# Controller.net
KiCad netlist of a schematic drawn in Altium Designer
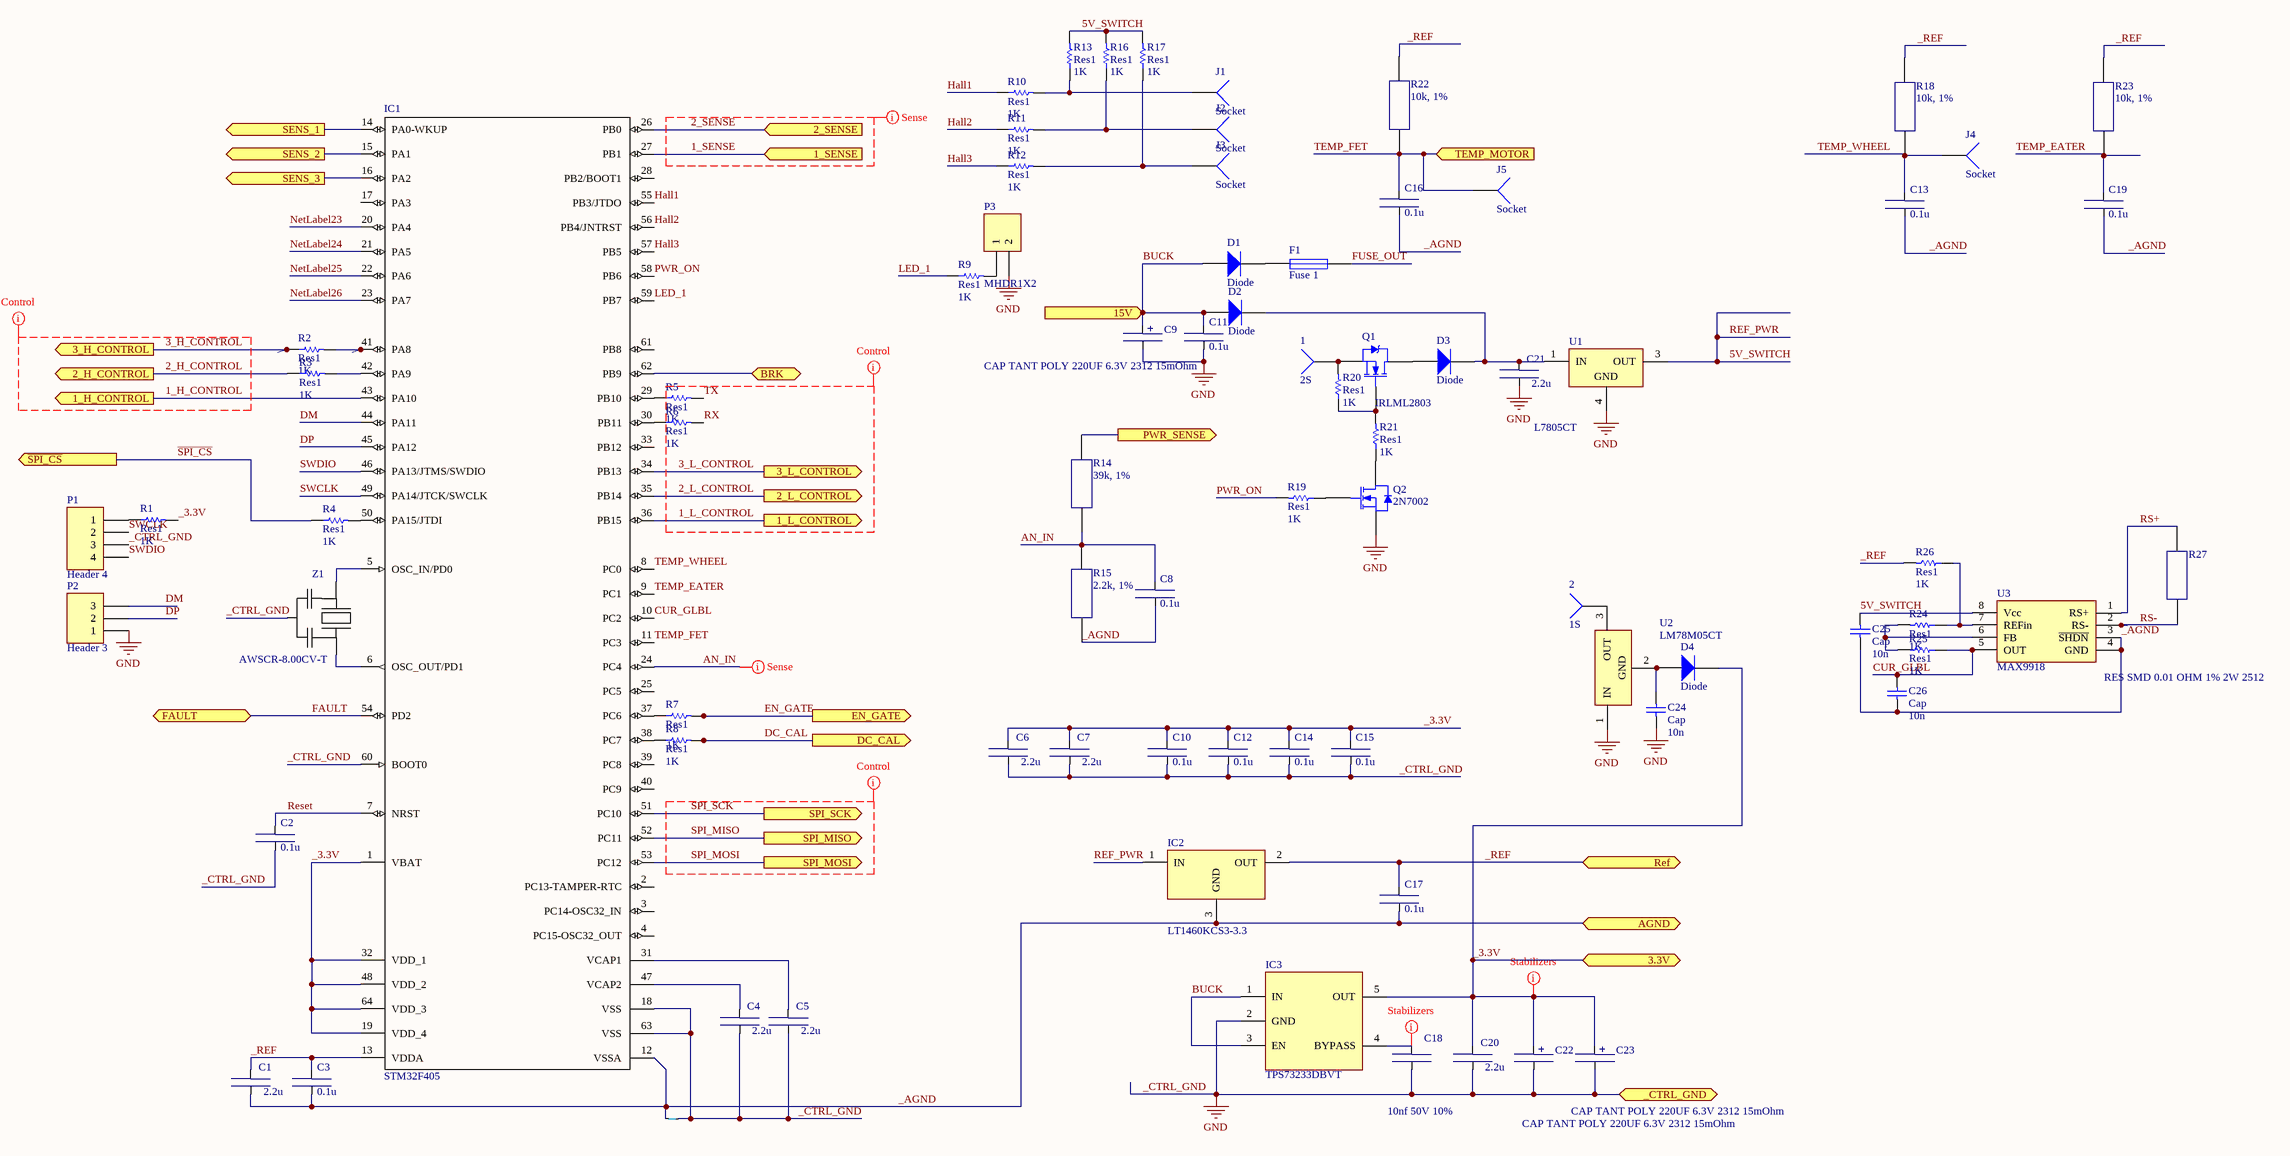
[diagram p0: Controller.SchDoc]

(export (version "E")
  (design (tool "Eeschema 10.0.6"))
  (components
    (comp (ref "1")
      (value "2S")
      (footprint "PIN1")
      (description "Socket")
      (fields (field (name "PUBLISHER") "Altium Limited"))
      (libsource (lib "Miscellaneous Connectors") (part "Socket"))
    )
    (comp (ref "2")
      (value "1S")
      (footprint "PIN1")
      (description "Socket")
      (fields (field (name "PUBLISHER") "Altium Limited"))
      (libsource (lib "Miscellaneous Connectors") (part "Socket"))
    )
    (comp (ref "C1")
      (value "2.2u")
      (footprint "ERA-0603")
      (libsource (lib "Condensator") (part "Ceramic Chip Capacitor"))
    )
    (comp (ref "C2")
      (value "0.1u")
      (footprint "Condensator:CAPC1608X08N(0603)")
      (libsource (lib "Condensator") (part "Ceramic Chip Capacitor"))
    )
    (comp (ref "C3")
      (value "0.1u")
      (footprint "ERA-0603")
      (libsource (lib "Condensator") (part "Ceramic Chip Capacitor"))
    )
    (comp (ref "C4")
      (value "2.2u")
      (footprint "Condensator:CAPC1608X08N(0603)")
      (libsource (lib "Condensator") (part "Ceramic Chip Capacitor"))
    )
    (comp (ref "C5")
      (value "2.2u")
      (footprint "Condensator:CAPC1608X08N(0603)")
      (libsource (lib "Condensator") (part "Ceramic Chip Capacitor"))
    )
    (comp (ref "C6")
      (value "2.2u")
      (footprint "Condensator:CAPC1608X08N(0603)")
      (libsource (lib "Condensator") (part "Ceramic Chip Capacitor"))
    )
    (comp (ref "C7")
      (value "2.2u")
      (footprint "Condensator:CAPC1608X08N(0603)")
      (libsource (lib "Condensator") (part "Ceramic Chip Capacitor"))
    )
    (comp (ref "C8")
      (value "0.1u")
      (footprint "0603x")
      (libsource (lib "Condensator") (part "Ceramic Chip Capacitor"))
    )
    (comp (ref "C9")
      (value "CAP TANT POLY 220UF 6.3V 2312 15mOhm")
      (footprint "CAP_POLY_330")
      (libsource (lib "Condensator") (part "Tantalum Chip Capacitor"))
    )
    (comp (ref "C10")
      (value "0.1u")
      (footprint "Condensator:CAPC1608X08N(0603)")
      (libsource (lib "Condensator") (part "Ceramic Chip Capacitor"))
    )
    (comp (ref "C11")
      (value "0.1u")
      (footprint "ERA-0603")
      (libsource (lib "Condensator") (part "Ceramic Chip Capacitor"))
    )
    (comp (ref "C12")
      (value "0.1u")
      (footprint "Condensator:CAPC1608X08N(0603)")
      (libsource (lib "Condensator") (part "Ceramic Chip Capacitor"))
    )
    (comp (ref "C13")
      (value "0.1u")
      (footprint "0603x")
      (libsource (lib "Condensator") (part "Ceramic Chip Capacitor"))
    )
    (comp (ref "C14")
      (value "0.1u")
      (footprint "Condensator:CAPC1608X08N(0603)")
      (libsource (lib "Condensator") (part "Ceramic Chip Capacitor"))
    )
    (comp (ref "C15")
      (value "0.1u")
      (footprint "Condensator:CAPC1608X08N(0603)")
      (libsource (lib "Condensator") (part "Ceramic Chip Capacitor"))
    )
    (comp (ref "C16")
      (value "0.1u")
      (footprint "Condensator:CAPC1608X08N(0603)")
      (libsource (lib "Condensator") (part "Ceramic Chip Capacitor"))
    )
    (comp (ref "C17")
      (value "0.1u")
      (footprint "0603x")
      (libsource (lib "Condensator") (part "Ceramic Chip Capacitor"))
    )
    (comp (ref "C18")
      (value "10nf 50V 10%")
      (footprint "0603x")
      (libsource (lib "Condensator") (part "Ceramic Chip Capacitor"))
    )
    (comp (ref "C19")
      (value "0.1u")
      (footprint "0603x")
      (libsource (lib "Condensator") (part "Ceramic Chip Capacitor"))
    )
    (comp (ref "C20")
      (value "2.2u")
      (footprint "Condensator:CAPC1608X08N(0603)")
      (libsource (lib "Condensator") (part "Ceramic Chip Capacitor"))
    )
    (comp (ref "C21")
      (value "2.2u")
      (footprint "0603x")
      (libsource (lib "Condensator") (part "Ceramic Chip Capacitor"))
    )
    (comp (ref "C22")
      (value "CAP TANT POLY 220UF 6.3V 2312 15mOhm")
      (footprint "C")
      (libsource (lib "Condensator") (part "Tantalum Chip Capacitor"))
    )
    (comp (ref "C23")
      (value "CAP TANT POLY 220UF 6.3V 2312 15mOhm")
      (footprint "CAP_POLY_330")
      (libsource (lib "Condensator") (part "Tantalum Chip Capacitor"))
    )
    (comp (ref "C24")
      (value "Cap")
      (footprint "ERA-0603")
      (description "Capacitor")
      (fields (field (name "ALTIUM_VALUE") "10n") (field (name "PUBLISHER") "Altium Limited"))
      (libsource (lib "Miscellaneous Devices") (part "Cap"))
    )
    (comp (ref "C25")
      (value "Cap")
      (footprint "ERA-0603")
      (description "Capacitor")
      (fields (field (name "ALTIUM_VALUE") "10n") (field (name "PUBLISHER") "Altium Limited"))
      (libsource (lib "Miscellaneous Devices") (part "Cap"))
    )
    (comp (ref "C26")
      (value "Cap")
      (footprint "ERA-0603")
      (description "Capacitor")
      (fields (field (name "ALTIUM_VALUE") "10n") (field (name "PUBLISHER") "Altium Limited"))
      (libsource (lib "Miscellaneous Devices") (part "Cap"))
    )
    (comp (ref "D1")
      (value "Diode")
      (footprint "SMB_real")
      (description "Default Diode")
      (fields (field (name "PUBLISHER") "Altium Limited"))
      (libsource (lib "Miscellaneous Devices") (part "Diode"))
    )
    (comp (ref "D2")
      (value "Diode")
      (footprint "SMA")
      (description "Default Diode")
      (fields (field (name "PUBLISHER") "Altium Limited"))
      (libsource (lib "Miscellaneous Devices") (part "Diode"))
    )
    (comp (ref "D3")
      (value "Diode")
      (footprint "SMA")
      (description "Default Diode")
      (fields (field (name "PUBLISHER") "Altium Limited"))
      (libsource (lib "Miscellaneous Devices") (part "Diode"))
    )
    (comp (ref "D4")
      (value "Diode")
      (footprint "SMA")
      (description "Default Diode")
      (fields (field (name "PUBLISHER") "Altium Limited"))
      (libsource (lib "Miscellaneous Devices") (part "Diode"))
    )
    (comp (ref "F1")
      (value "Fuse 1")
      (footprint "1812")
      (description "Fuse")
      (fields (field (name "PUBLISHER") "Altium Limited"))
      (libsource (lib "Miscellaneous Devices") (part "Fuse 1"))
    )
    (comp (ref "IC1")
      (value "STM32F405")
      (footprint "LQFP64_L")
      (description "STM32 ARM-based 32-bit MCU")
      (libsource (lib "Mikrosxema") (part "STM32F405"))
    )
    (comp (ref "IC2")
      (value "LT1460KCS3-3.3")
      (footprint "SOT23-3_L")
      (libsource (lib "CustomLib") (part "PreciseRef"))
    )
    (comp (ref "IC3")
      (value "TPS73233DBVT")
      (footprint "SOT23-5_L")
      (libsource (lib "CustomLib") (part "TPS7xx33"))
    )
    (comp (ref "J1")
      (value "Socket")
      (footprint "PIN1")
      (fields (field (name "PUBLISHER") "Altium Limited"))
      (libsource (lib "Miscellaneous Connectors") (part "Socket"))
    )
    (comp (ref "J2")
      (value "Socket")
      (footprint "PIN1")
      (fields (field (name "PUBLISHER") "Altium Limited"))
      (libsource (lib "Miscellaneous Connectors") (part "Socket"))
    )
    (comp (ref "J3")
      (value "Socket")
      (footprint "PIN1")
      (fields (field (name "PUBLISHER") "Altium Limited"))
      (libsource (lib "Miscellaneous Connectors") (part "Socket"))
    )
    (comp (ref "J4")
      (value "Socket")
      (footprint "PIN1")
      (fields (field (name "PUBLISHER") "Altium Limited"))
      (libsource (lib "Miscellaneous Connectors") (part "Socket"))
    )
    (comp (ref "J5")
      (value "Socket")
      (footprint "PIN1")
      (fields (field (name "PUBLISHER") "Altium Limited"))
      (libsource (lib "Miscellaneous Connectors") (part "Socket"))
    )
    (comp (ref "NT1")
      (value "NET_TIE")
      (footprint "NET_TIE_10mil")
      (description "Net tie")
      (libsource (lib "CustomLib") (part "Net tie"))
    )
    (comp (ref "P1")
      (value "Header 4")
      (footprint "MHDR1X4")
      (description "Header, 4-Pin")
      (fields (field (name "PUBLISHER") "Altium Limited"))
      (libsource (lib "Miscellaneous Connectors") (part "Header 4"))
    )
    (comp (ref "P2")
      (value "Header 3")
      (footprint "HDR1X3")
      (description "Header, 3-Pin")
      (fields (field (name "PUBLISHER") "Altium Limited"))
      (libsource (lib "Miscellaneous Connectors") (part "Header 3"))
    )
    (comp (ref "P3")
      (value "MHDR1X2")
      (footprint "MHDR1X2")
      (description "Header, 2-Pin")
      (fields (field (name "PUBLISHER") "Altium Limited"))
      (libsource (lib "Miscellaneous Connectors") (part "MHDR1X2"))
    )
    (comp (ref "Q1")
      (value "IRLML2803")
      (footprint "SOT-23_N")
      (description "HEXFET Power MOSFET")
      (fields (field (name "PUBLISHER") "Altium Limited"))
      (libsource (lib "IR Discrete MOSFET - Power") (part "IRLML2803"))
    )
    (comp (ref "Q2")
      (value "2N7002")
      (footprint "SOT23_N")
      (description "N-channel Enhancement Mode Field-effect Transistor")
      (fields (field (name "PUBLISHER") "Altium Limited"))
      (libsource (lib "Philips Discrete MOSFET - Low Power") (part "2N7002"))
    )
    (comp (ref "R1")
      (value "Res1")
      (footprint "0603x")
      (description "Resistor")
      (fields (field (name "ALTIUM_VALUE") "1K") (field (name "PUBLISHER") "Altium Limited"))
      (libsource (lib "Miscellaneous Devices") (part "Res1"))
    )
    (comp (ref "R2")
      (value "Res1")
      (footprint "1206x")
      (description "Resistor")
      (fields (field (name "ALTIUM_VALUE") "1K") (field (name "PUBLISHER") "Altium Limited"))
      (libsource (lib "Miscellaneous Devices") (part "Res1"))
    )
    (comp (ref "R3")
      (value "Res1")
      (footprint "0603x")
      (description "Resistor")
      (fields (field (name "ALTIUM_VALUE") "1K") (field (name "PUBLISHER") "Altium Limited"))
      (libsource (lib "Miscellaneous Devices") (part "Res1"))
    )
    (comp (ref "R4")
      (value "Res1")
      (footprint "0603x")
      (description "Resistor")
      (fields (field (name "ALTIUM_VALUE") "1K") (field (name "PUBLISHER") "Altium Limited"))
      (libsource (lib "Miscellaneous Devices") (part "Res1"))
    )
    (comp (ref "R5")
      (value "Res1")
      (footprint "0402x")
      (description "Resistor")
      (fields (field (name "ALTIUM_VALUE") "1K") (field (name "PUBLISHER") "Altium Limited"))
      (libsource (lib "Miscellaneous Devices") (part "Res1"))
    )
    (comp (ref "R6")
      (value "Res1")
      (footprint "0402x")
      (description "Resistor")
      (fields (field (name "ALTIUM_VALUE") "1K") (field (name "PUBLISHER") "Altium Limited"))
      (libsource (lib "Miscellaneous Devices") (part "Res1"))
    )
    (comp (ref "R7")
      (value "Res1")
      (footprint "0805x")
      (description "Resistor")
      (fields (field (name "ALTIUM_VALUE") "1K") (field (name "PUBLISHER") "Altium Limited"))
      (libsource (lib "Miscellaneous Devices") (part "Res1"))
    )
    (comp (ref "R8")
      (value "Res1")
      (footprint "0603x")
      (description "Resistor")
      (fields (field (name "ALTIUM_VALUE") "1K") (field (name "PUBLISHER") "Altium Limited"))
      (libsource (lib "Miscellaneous Devices") (part "Res1"))
    )
    (comp (ref "R9")
      (value "Res1")
      (footprint "0603x")
      (description "Resistor")
      (fields (field (name "ALTIUM_VALUE") "1K") (field (name "PUBLISHER") "Altium Limited"))
      (libsource (lib "Miscellaneous Devices") (part "Res1"))
    )
    (comp (ref "R10")
      (value "Res1")
      (footprint "0603x")
      (description "Resistor")
      (fields (field (name "ALTIUM_VALUE") "1K") (field (name "PUBLISHER") "Altium Limited"))
      (libsource (lib "Miscellaneous Devices") (part "Res1"))
    )
    (comp (ref "R11")
      (value "Res1")
      (footprint "0603x")
      (description "Resistor")
      (fields (field (name "ALTIUM_VALUE") "1K") (field (name "PUBLISHER") "Altium Limited"))
      (libsource (lib "Miscellaneous Devices") (part "Res1"))
    )
    (comp (ref "R12")
      (value "Res1")
      (footprint "0603x")
      (description "Resistor")
      (fields (field (name "ALTIUM_VALUE") "1K") (field (name "PUBLISHER") "Altium Limited"))
      (libsource (lib "Miscellaneous Devices") (part "Res1"))
    )
    (comp (ref "R13")
      (value "Res1")
      (footprint "0603x")
      (description "Resistor")
      (fields (field (name "ALTIUM_VALUE") "1K") (field (name "PUBLISHER") "Altium Limited"))
      (libsource (lib "Miscellaneous Devices") (part "Res1"))
    )
    (comp (ref "R14") (value "39k, 1%") (footprint "1206x") (libsource (lib "Rezistor") (part "SMD")))
    (comp (ref "R15") (value "2.2k, 1%") (footprint "0603x") (libsource (lib "Rezistor") (part "SMD")))
    (comp (ref "R16")
      (value "Res1")
      (footprint "0603x")
      (description "Resistor")
      (fields (field (name "ALTIUM_VALUE") "1K") (field (name "PUBLISHER") "Altium Limited"))
      (libsource (lib "Miscellaneous Devices") (part "Res1"))
    )
    (comp (ref "R17")
      (value "Res1")
      (footprint "0603x")
      (description "Resistor")
      (fields (field (name "ALTIUM_VALUE") "1K") (field (name "PUBLISHER") "Altium Limited"))
      (libsource (lib "Miscellaneous Devices") (part "Res1"))
    )
    (comp (ref "R18") (value "10k, 1%") (footprint "0603x") (libsource (lib "Rezistor") (part "SMD")))
    (comp (ref "R19")
      (value "Res1")
      (footprint "0603x")
      (description "Resistor")
      (fields (field (name "ALTIUM_VALUE") "1K") (field (name "PUBLISHER") "Altium Limited"))
      (libsource (lib "Miscellaneous Devices") (part "Res1"))
    )
    (comp (ref "R20")
      (value "Res1")
      (footprint "0603x")
      (description "Resistor")
      (fields (field (name "ALTIUM_VALUE") "1K") (field (name "PUBLISHER") "Altium Limited"))
      (libsource (lib "Miscellaneous Devices") (part "Res1"))
    )
    (comp (ref "R21")
      (value "Res1")
      (footprint "0603x")
      (description "Resistor")
      (fields (field (name "ALTIUM_VALUE") "1K") (field (name "PUBLISHER") "Altium Limited"))
      (libsource (lib "Miscellaneous Devices") (part "Res1"))
    )
    (comp (ref "R22")
      (value "10k, 1%")
      (footprint "Rezistor:RESC1608X05N(0603)")
      (libsource (lib "Rezistor") (part "SMD"))
    )
    (comp (ref "R23") (value "10k, 1%") (footprint "0603x") (libsource (lib "Rezistor") (part "SMD")))
    (comp (ref "R24")
      (value "Res1")
      (footprint "0603x")
      (description "Resistor")
      (fields (field (name "ALTIUM_VALUE") "1K") (field (name "PUBLISHER") "Altium Limited"))
      (libsource (lib "Miscellaneous Devices") (part "Res1"))
    )
    (comp (ref "R25")
      (value "Res1")
      (footprint "0603x")
      (description "Resistor")
      (fields (field (name "ALTIUM_VALUE") "1K") (field (name "PUBLISHER") "Altium Limited"))
      (libsource (lib "Miscellaneous Devices") (part "Res1"))
    )
    (comp (ref "R26")
      (value "Res1")
      (footprint "0603x")
      (description "Resistor")
      (fields (field (name "ALTIUM_VALUE") "1K") (field (name "PUBLISHER") "Altium Limited"))
      (libsource (lib "Miscellaneous Devices") (part "Res1"))
    )
    (comp (ref "R27")
      (value "RES SMD 0.01 OHM 1% 2W 2512")
      (footprint "1T-2512")
      (libsource (lib "Rezistor") (part "SMD"))
    )
    (comp (ref "U1")
      (value "L7805CT")
      (footprint "TO-252AA")
      (description "Positive Voltage Regulator")
      (fields (field (name "PUBLISHER") "Altium Limited"))
      (libsource (lib "ST Power Mgt Voltage Regulator") (part "L7805CT"))
    )
    (comp (ref "U2")
      (value "LM78M05CT")
      (footprint "318-08")
      (description "3-Terminal Positive Voltage Regulators, 3-pin TO-220")
      (fields
        (field (name "MANUFACTURER") "National Semiconductor")
        (field (name "PUBLISHER") "Altium Limited")
      )
      (libsource (lib "NSC LDO") (part "LM78M05CT"))
    )
    (comp (ref "U3") (value "MAX9918") (footprint "SO8_M") (libsource (lib "CustomLib") (part "MAX9918")))
    (comp (ref "Z1")
      (value "AWSCR-8.00CV-T")
      (footprint "CRYSTAL_CERAMIC")
      (libsource (lib "CustomLib") (part "Crystal_smd_with_caps"))
    )
  )
  (nets
    (net (code "1") (name "/1_H_CONTROL") (class "Default")
      (node (ref "IC1") (pin "43") (pinfunction "PA10_43") (pintype "bidirectional"))
    )
    (net (code "2") (name "/1_L_CONTROL") (class "Default")
      (node (ref "IC1") (pin "36") (pinfunction "PB15_36") (pintype "bidirectional"))
    )
    (net (code "3") (name "/1_SENSE") (class "Default")
      (node (ref "IC1") (pin "27") (pinfunction "PB1_27") (pintype "bidirectional"))
    )
    (net (code "4") (name "/2_H_CONTROL") (class "Default")
      (node (ref "R3") (pin "1") (pinfunction "1_1") (pintype "passive"))
    )
    (net (code "5") (name "/2_L_CONTROL") (class "Default")
      (node (ref "IC1") (pin "35") (pinfunction "PB14_35") (pintype "bidirectional"))
    )
    (net (code "6") (name "/2_SENSE") (class "Default")
      (node (ref "IC1") (pin "26") (pinfunction "PB0_26") (pintype "bidirectional"))
    )
    (net (code "7") (name "/3_H_CONTROL") (class "Default")
      (node (ref "R2") (pin "1") (pinfunction "1_1") (pintype "passive"))
    )
    (net (code "8") (name "/3_L_CONTROL") (class "Default")
      (node (ref "IC1") (pin "34") (pinfunction "PB13_34") (pintype "bidirectional"))
    )
    (net (code "9") (name "/5V_SWITCH") (class "Default")
      (node (ref "C25") (pin "1") (pinfunction "1_1") (pintype "passive"))
      (node (ref "IC2") (pin "1") (pinfunction "IN_1") (pintype "passive"))
      (node (ref "R13") (pin "2") (pinfunction "2_2") (pintype "passive"))
      (node (ref "R16") (pin "2") (pinfunction "2_2") (pintype "passive"))
      (node (ref "R17") (pin "2") (pinfunction "2_2") (pintype "passive"))
      (node (ref "U1") (pin "3") (pinfunction "OUT_3") (pintype "power_in"))
      (node (ref "U3") (pin "8") (pinfunction "Vcc_8") (pintype "passive"))
    )
    (net (code "10") (name "/AN_IN") (class "Default")
      (node (ref "C8") (pin "1") (pintype "passive"))
      (node (ref "IC1") (pin "24") (pinfunction "PC4_24") (pintype "bidirectional"))
      (node (ref "R14") (pin "2") (pintype "passive"))
      (node (ref "R15") (pin "1") (pintype "passive"))
    )
    (net (code "11") (name "/BRK") (class "Default")
      (node (ref "IC1") (pin "62") (pinfunction "PB9_62") (pintype "bidirectional"))
    )
    (net (code "12") (name "/BUCK") (class "Default")
      (node (ref "C11") (pin "1") (pintype "passive"))
      (node (ref "C9") (pin "1") (pintype "passive"))
      (node (ref "D1") (pin "1") (pinfunction "A_1") (pintype "passive"))
      (node (ref "D2") (pin "1") (pinfunction "A_1") (pintype "passive"))
      (node (ref "IC3") (pin "1") (pinfunction "IN_1") (pintype "passive"))
      (node (ref "IC3") (pin "3") (pinfunction "EN_3") (pintype "passive"))
    )
    (net (code "13") (name "/CUR_GLBL") (class "Default")
      (node (ref "C26") (pin "1") (pinfunction "1_1") (pintype "passive"))
      (node (ref "IC1") (pin "10") (pinfunction "PC2_10") (pintype "bidirectional"))
      (node (ref "R25") (pin "1") (pinfunction "1_1") (pintype "passive"))
      (node (ref "U3") (pin "5") (pinfunction "OUT_5") (pintype "passive"))
    )
    (net (code "14") (name "/DC_CAL") (class "Default")
      (node (ref "R8") (pin "2") (pinfunction "2_2") (pintype "passive"))
    )
    (net (code "15") (name "/DM") (class "Default")
      (node (ref "IC1") (pin "44") (pinfunction "PA11_44") (pintype "bidirectional"))
      (node (ref "P2") (pin "3") (pinfunction "3_3") (pintype "passive"))
    )
    (net (code "16") (name "/DP") (class "Default")
      (node (ref "IC1") (pin "45") (pinfunction "PA12_45") (pintype "bidirectional"))
      (node (ref "P2") (pin "2") (pinfunction "2_2") (pintype "passive"))
    )
    (net (code "17") (name "/EN_GATE") (class "Default")
      (node (ref "R7") (pin "2") (pinfunction "2_2") (pintype "passive"))
    )
    (net (code "18") (name "/FAULT") (class "Default")
      (node (ref "IC1") (pin "54") (pinfunction "PD2_54") (pintype "bidirectional"))
    )
    (net (code "19") (name "/FUSE_OUT") (class "Default")
      (node (ref "F1") (pin "2") (pinfunction "2_2") (pintype "passive"))
    )
    (net (code "20") (name "/Hall1") (class "Default")
      (node (ref "IC1") (pin "55") (pinfunction "PB3/JTDO_55") (pintype "bidirectional"))
      (node (ref "R10") (pin "1") (pinfunction "1_1") (pintype "passive"))
    )
    (net (code "21") (name "/Hall2") (class "Default")
      (node (ref "IC1") (pin "56") (pinfunction "PB4/JNTRST_56") (pintype "bidirectional"))
      (node (ref "R11") (pin "1") (pinfunction "1_1") (pintype "passive"))
    )
    (net (code "22") (name "/Hall3") (class "Default")
      (node (ref "IC1") (pin "57") (pinfunction "PB5_57") (pintype "bidirectional"))
      (node (ref "R12") (pin "1") (pinfunction "1_1") (pintype "passive"))
    )
    (net (code "23") (name "/LED_1") (class "Default")
      (node (ref "IC1") (pin "59") (pinfunction "PB7_59") (pintype "bidirectional"))
      (node (ref "R9") (pin "1") (pinfunction "1_1") (pintype "passive"))
    )
    (net (code "24") (name "/NetLabel23") (class "Default")
      (node (ref "IC1") (pin "20") (pinfunction "PA4_20") (pintype "bidirectional"))
    )
    (net (code "25") (name "/NetLabel24") (class "Default")
      (node (ref "IC1") (pin "21") (pinfunction "PA5_21") (pintype "bidirectional"))
    )
    (net (code "26") (name "/NetLabel25") (class "Default")
      (node (ref "IC1") (pin "22") (pinfunction "PA6_22") (pintype "bidirectional"))
    )
    (net (code "27") (name "/NetLabel26") (class "Default")
      (node (ref "IC1") (pin "23") (pinfunction "PA7_23") (pintype "bidirectional"))
    )
    (net (code "28") (name "/PWR_ON") (class "Default")
      (node (ref "IC1") (pin "58") (pinfunction "PB6_58") (pintype "bidirectional"))
      (node (ref "R19") (pin "2") (pinfunction "2_2") (pintype "passive"))
    )
    (net (code "29") (name "/PWR_SENSE") (class "Default") (node (ref "R14") (pin "1") (pintype "passive")))
    (net (code "30") (name "/RS+") (class "Default")
      (node (ref "R27") (pin "1") (pintype "passive"))
      (node (ref "U3") (pin "1") (pinfunction "RS+_1") (pintype "passive"))
    )
    (net (code "32") (name "/RX") (class "Default")
      (node (ref "R6") (pin "2") (pinfunction "2_2") (pintype "passive"))
    )
    (net (code "33") (name "/Reset") (class "Default")
      (node (ref "C2") (pin "1") (pintype "passive"))
      (node (ref "IC1") (pin "7") (pinfunction "NRST_7") (pintype "bidirectional"))
    )
    (net (code "34") (name "/SENS_1") (class "Default")
      (node (ref "IC1") (pin "14") (pinfunction "PA0-WKUP_14") (pintype "bidirectional"))
    )
    (net (code "35") (name "/SENS_2") (class "Default")
      (node (ref "IC1") (pin "15") (pinfunction "PA1_15") (pintype "bidirectional"))
    )
    (net (code "36") (name "/SENS_3") (class "Default")
      (node (ref "IC1") (pin "16") (pinfunction "PA2_16") (pintype "bidirectional"))
    )
    (net (code "37") (name "/SPI_MISO") (class "Default")
      (node (ref "IC1") (pin "52") (pinfunction "PC11_52") (pintype "bidirectional"))
    )
    (net (code "38") (name "/SPI_MOSI") (class "Default")
      (node (ref "IC1") (pin "53") (pinfunction "PC12_53") (pintype "bidirectional"))
    )
    (net (code "39") (name "/SPI_SCK") (class "Default")
      (node (ref "IC1") (pin "51") (pinfunction "PC10_51") (pintype "bidirectional"))
    )
    (net (code "40") (name "/SWCLK") (class "Default")
      (node (ref "IC1") (pin "49") (pinfunction "PA14/JTCK/SWCLK_49") (pintype "bidirectional"))
      (node (ref "P1") (pin "2") (pinfunction "2_2") (pintype "passive"))
    )
    (net (code "41") (name "/SWDIO") (class "Default")
      (node (ref "IC1") (pin "46") (pinfunction "PA13/JTMS/SWDIO_46") (pintype "bidirectional"))
      (node (ref "P1") (pin "4") (pinfunction "4_4") (pintype "passive"))
    )
    (net (code "42") (name "/TEMP_EATER") (class "Default")
      (node (ref "C19") (pin "1") (pintype "passive"))
      (node (ref "IC1") (pin "9") (pinfunction "PC1_9") (pintype "bidirectional"))
      (node (ref "R23") (pin "2") (pintype "passive"))
    )
    (net (code "43") (name "/TEMP_FET") (class "Default")
      (node (ref "C16") (pin "1") (pintype "passive"))
      (node (ref "IC1") (pin "11") (pinfunction "PC3_11") (pintype "bidirectional"))
      (node (ref "J5") (pin "1") (pinfunction "1_1") (pintype "passive"))
      (node (ref "R22") (pin "2") (pintype "passive"))
    )
    (net (code "44") (name "/TEMP_WHEEL") (class "Default")
      (node (ref "C13") (pin "1") (pintype "passive"))
      (node (ref "IC1") (pin "8") (pinfunction "PC0_8") (pintype "bidirectional"))
      (node (ref "J4") (pin "1") (pinfunction "1_1") (pintype "passive"))
      (node (ref "R18") (pin "2") (pintype "passive"))
    )
    (net (code "45") (name "/TX") (class "Default")
      (node (ref "R5") (pin "2") (pinfunction "2_2") (pintype "passive"))
    )
    (net (code "46") (name "/_3.3V") (class "Default")
      (node (ref "C10") (pin "1") (pintype "passive"))
      (node (ref "C12") (pin "1") (pintype "passive"))
      (node (ref "C14") (pin "1") (pintype "passive"))
      (node (ref "C15") (pin "1") (pintype "passive"))
      (node (ref "C20") (pin "1") (pintype "passive"))
      (node (ref "C22") (pin "1") (pintype "passive"))
      (node (ref "C23") (pin "1") (pintype "passive"))
      (node (ref "C6") (pin "1") (pintype "passive"))
      (node (ref "C7") (pin "1") (pintype "passive"))
      (node (ref "D4") (pin "2") (pinfunction "K_2") (pintype "passive"))
      (node (ref "IC1") (pin "1") (pinfunction "VBAT_1") (pintype "power_in"))
      (node (ref "IC1") (pin "19") (pinfunction "VDD_4_19") (pintype "power_in"))
      (node (ref "IC1") (pin "32") (pinfunction "VDD_1_32") (pintype "power_in"))
      (node (ref "IC1") (pin "48") (pinfunction "VDD_2_48") (pintype "power_in"))
      (node (ref "IC1") (pin "64") (pinfunction "VDD_3_64") (pintype "power_in"))
      (node (ref "IC3") (pin "5") (pinfunction "OUT_5") (pintype "passive"))
      (node (ref "R1") (pin "2") (pinfunction "2_2") (pintype "passive"))
    )
    (net (code "47") (name "/_AGND") (class "Default")
      (node (ref "C1") (pin "2") (pintype "passive"))
      (node (ref "C13") (pin "2") (pintype "passive"))
      (node (ref "C16") (pin "2") (pintype "passive"))
      (node (ref "C17") (pin "2") (pintype "passive"))
      (node (ref "C19") (pin "2") (pintype "passive"))
      (node (ref "C25") (pin "2") (pinfunction "2_2") (pintype "passive"))
      (node (ref "C26") (pin "2") (pinfunction "2_2") (pintype "passive"))
      (node (ref "C3") (pin "2") (pintype "passive"))
      (node (ref "C8") (pin "2") (pintype "passive"))
      (node (ref "IC1") (pin "12") (pinfunction "VSSA_12") (pintype "power_in"))
      (node (ref "IC2") (pin "3") (pinfunction "GND_3") (pintype "passive"))
      (node (ref "NT1") (pin "1") (pinfunction "1_1") (pintype "passive"))
      (node (ref "R15") (pin "2") (pintype "passive"))
      (node (ref "U3") (pin "3") (pinfunction "~{SHDN}_3") (pintype "passive"))
      (node (ref "U3") (pin "4") (pinfunction "GND_4") (pintype "passive"))
    )
    (net (code "48") (name "/_REF") (class "Default")
      (node (ref "C1") (pin "1") (pintype "passive"))
      (node (ref "C17") (pin "1") (pintype "passive"))
      (node (ref "C3") (pin "1") (pintype "passive"))
      (node (ref "IC1") (pin "13") (pinfunction "VDDA_13") (pintype "power_in"))
      (node (ref "IC2") (pin "2") (pinfunction "OUT_2") (pintype "passive"))
      (node (ref "R18") (pin "1") (pintype "passive"))
      (node (ref "R22") (pin "1") (pintype "passive"))
      (node (ref "R23") (pin "1") (pintype "passive"))
      (node (ref "R26") (pin "2") (pinfunction "2_2") (pintype "passive"))
    )
    (net (code "49") (name "/~{SPI_CS}") (class "Default")
      (node (ref "R4") (pin "1") (pinfunction "1_1") (pintype "passive"))
    )
    (net (code "50") (name "GND") (class "Default")
      (node (ref "C10") (pin "2") (pintype "passive"))
      (node (ref "C11") (pin "2") (pintype "passive"))
      (node (ref "C12") (pin "2") (pintype "passive"))
      (node (ref "C14") (pin "2") (pintype "passive"))
      (node (ref "C15") (pin "2") (pintype "passive"))
      (node (ref "C18") (pin "2") (pintype "passive"))
      (node (ref "C2") (pin "2") (pintype "passive"))
      (node (ref "C20") (pin "2") (pintype "passive"))
      (node (ref "C21") (pin "2") (pintype "passive"))
      (node (ref "C22") (pin "2") (pintype "passive"))
      (node (ref "C23") (pin "2") (pintype "passive"))
      (node (ref "C24") (pin "2") (pinfunction "2_2") (pintype "passive"))
      (node (ref "C4") (pin "2") (pintype "passive"))
      (node (ref "C5") (pin "2") (pintype "passive"))
      (node (ref "C6") (pin "2") (pintype "passive"))
      (node (ref "C7") (pin "2") (pintype "passive"))
      (node (ref "C9") (pin "2") (pintype "passive"))
      (node (ref "IC1") (pin "18") (pinfunction "VSS_18") (pintype "passive"))
      (node (ref "IC1") (pin "60") (pinfunction "BOOT0_60") (pintype "input"))
      (node (ref "IC1") (pin "63") (pinfunction "VSS_63") (pintype "power_in"))
      (node (ref "IC3") (pin "2") (pinfunction "GND_2") (pintype "passive"))
      (node (ref "NT1") (pin "2") (pinfunction "2_2") (pintype "passive"))
      (node (ref "P1") (pin "3") (pinfunction "3_3") (pintype "passive"))
      (node (ref "P2") (pin "1") (pinfunction "1_1") (pintype "passive"))
      (node (ref "P3") (pin "2") (pinfunction "2_2") (pintype "passive"))
      (node (ref "Q2") (pin "2") (pinfunction "S_2") (pintype "passive"))
      (node (ref "U1") (pin "4") (pinfunction "GND_4") (pintype "power_in"))
      (node (ref "U2") (pin "1") (pinfunction "IN_1") (pintype "power_in"))
      (node (ref "Z1") (pin "2") (pinfunction "GND_2") (pintype "passive"))
    )
    (net (code "51") (name "Net-(D1-K)") (class "Default")
      (node (ref "D1") (pin "2") (pinfunction "K_2") (pintype "passive"))
      (node (ref "F1") (pin "1") (pinfunction "1_1") (pintype "passive"))
    )
    (net (code "52") (name "Net-(D2-K)") (class "Default")
      (node (ref "C21") (pin "1") (pintype "passive"))
      (node (ref "D2") (pin "2") (pinfunction "K_2") (pintype "passive"))
      (node (ref "D3") (pin "2") (pinfunction "K_2") (pintype "passive"))
      (node (ref "U1") (pin "1") (pinfunction "IN_1") (pintype "power_in"))
    )
    (net (code "53") (name "Net-(D3-A)") (class "Default")
      (node (ref "D3") (pin "1") (pinfunction "A_1") (pintype "passive"))
      (node (ref "Q1") (pin "3") (pinfunction "D_3") (pintype "passive"))
    )
    (net (code "54") (name "Net-(D4-A)") (class "Default")
      (node (ref "C24") (pin "1") (pinfunction "1_1") (pintype "passive"))
      (node (ref "D4") (pin "1") (pinfunction "A_1") (pintype "passive"))
      (node (ref "U2") (pin "2") (pinfunction "GND_2") (pintype "power_in"))
    )
    (net (code "55") (name "Net-(IC1-OSC_IN{slash}PD0)") (class "Default")
      (node (ref "IC1") (pin "5") (pinfunction "OSC_IN/PD0_5") (pintype "input"))
      (node (ref "Z1") (pin "1") (pinfunction "X1_1") (pintype "passive"))
    )
    (net (code "56") (name "Net-(IC1-OSC_OUT{slash}PD1)") (class "Default")
      (node (ref "IC1") (pin "6") (pinfunction "OSC_OUT/PD1_6") (pintype "output"))
      (node (ref "Z1") (pin "3") (pinfunction "X2_3") (pintype "passive"))
    )
    (net (code "57") (name "Net-(IC1-PA8)") (class "Default")
      (node (ref "IC1") (pin "41") (pinfunction "PA8_41") (pintype "bidirectional"))
      (node (ref "R2") (pin "2") (pinfunction "2_2") (pintype "passive"))
    )
    (net (code "58") (name "Net-(IC1-PA9)") (class "Default")
      (node (ref "IC1") (pin "42") (pinfunction "PA9_42") (pintype "bidirectional"))
      (node (ref "R3") (pin "2") (pinfunction "2_2") (pintype "passive"))
    )
    (net (code "59") (name "Net-(IC1-PA15{slash}JTDI)") (class "Default")
      (node (ref "IC1") (pin "50") (pinfunction "PA15/JTDI_50") (pintype "bidirectional"))
      (node (ref "R4") (pin "2") (pinfunction "2_2") (pintype "passive"))
    )
    (net (code "60") (name "Net-(IC1-PB10)") (class "Default")
      (node (ref "IC1") (pin "29") (pinfunction "PB10_29") (pintype "bidirectional"))
      (node (ref "R5") (pin "1") (pinfunction "1_1") (pintype "passive"))
    )
    (net (code "61") (name "Net-(IC1-PB11)") (class "Default")
      (node (ref "IC1") (pin "30") (pinfunction "PB11_30") (pintype "bidirectional"))
      (node (ref "R6") (pin "1") (pinfunction "1_1") (pintype "passive"))
    )
    (net (code "62") (name "Net-(IC1-PC6)") (class "Default")
      (node (ref "IC1") (pin "37") (pinfunction "PC6_37") (pintype "bidirectional"))
      (node (ref "R7") (pin "1") (pinfunction "1_1") (pintype "passive"))
    )
    (net (code "63") (name "Net-(IC1-PC7)") (class "Default")
      (node (ref "IC1") (pin "38") (pinfunction "PC7_38") (pintype "bidirectional"))
      (node (ref "R8") (pin "1") (pinfunction "1_1") (pintype "passive"))
    )
    (net (code "64") (name "Net-(IC1-VCAP1)") (class "Default")
      (node (ref "C5") (pin "1") (pintype "passive"))
      (node (ref "IC1") (pin "31") (pinfunction "VCAP1_31") (pintype "power_in"))
    )
    (net (code "65") (name "Net-(IC1-VCAP2)") (class "Default")
      (node (ref "C4") (pin "1") (pintype "passive"))
      (node (ref "IC1") (pin "47") (pinfunction "VCAP2_47") (pintype "power_in"))
    )
    (net (code "66") (name "Net-(IC3-BYPASS)") (class "Default")
      (node (ref "C18") (pin "1") (pintype "passive"))
      (node (ref "IC3") (pin "4") (pinfunction "BYPASS_4") (pintype "passive"))
    )
    (net (code "67") (name "Net-(J1-Pad1)") (class "Default")
      (node (ref "J1") (pin "1") (pinfunction "1_1") (pintype "passive"))
      (node (ref "R10") (pin "2") (pinfunction "2_2") (pintype "passive"))
      (node (ref "R13") (pin "1") (pinfunction "1_1") (pintype "passive"))
    )
    (net (code "68") (name "Net-(J2-Pad1)") (class "Default")
      (node (ref "J2") (pin "1") (pinfunction "1_1") (pintype "passive"))
      (node (ref "R11") (pin "2") (pinfunction "2_2") (pintype "passive"))
      (node (ref "R16") (pin "1") (pinfunction "1_1") (pintype "passive"))
    )
    (net (code "69") (name "Net-(J3-Pad1)") (class "Default")
      (node (ref "J3") (pin "1") (pinfunction "1_1") (pintype "passive"))
      (node (ref "R12") (pin "2") (pinfunction "2_2") (pintype "passive"))
      (node (ref "R17") (pin "1") (pinfunction "1_1") (pintype "passive"))
    )
    (net (code "70") (name "Net-(P1-Pad1)") (class "Default")
      (node (ref "P1") (pin "1") (pinfunction "1_1") (pintype "passive"))
      (node (ref "R1") (pin "1") (pinfunction "1_1") (pintype "passive"))
    )
    (net (code "71") (name "Net-(P3-Pad1)") (class "Default")
      (node (ref "P3") (pin "1") (pinfunction "1_1") (pintype "passive"))
      (node (ref "R9") (pin "2") (pinfunction "2_2") (pintype "passive"))
    )
    (net (code "72") (name "Net-(Q1-G)") (class "Default")
      (node (ref "Q1") (pin "1") (pinfunction "G_1") (pintype "passive"))
      (node (ref "R20") (pin "1") (pinfunction "1_1") (pintype "passive"))
      (node (ref "R21") (pin "2") (pinfunction "2_2") (pintype "passive"))
    )
    (net (code "73") (name "Net-(Q1-S)") (class "Default")
      (node (ref "1") (pin "1") (pinfunction "1_1") (pintype "passive"))
      (node (ref "Q1") (pin "2") (pinfunction "S_2") (pintype "passive"))
      (node (ref "R20") (pin "2") (pinfunction "2_2") (pintype "passive"))
    )
    (net (code "74") (name "Net-(Q2-D)") (class "Default")
      (node (ref "Q2") (pin "3") (pinfunction "D_3") (pintype "passive"))
      (node (ref "R21") (pin "1") (pinfunction "1_1") (pintype "passive"))
    )
    (net (code "75") (name "Net-(Q2-G)") (class "Default")
      (node (ref "Q2") (pin "1") (pinfunction "G_1") (pintype "passive"))
      (node (ref "R19") (pin "1") (pinfunction "1_1") (pintype "passive"))
    )
    (net (code "76") (name "Net-(U2-OUT)") (class "Default")
      (node (ref "2") (pin "1") (pinfunction "1_1") (pintype "passive"))
      (node (ref "U2") (pin "3") (pinfunction "OUT_3") (pintype "power_in"))
    )
    (net (code "77") (name "Net-(U3-FB)") (class "Default")
      (node (ref "R24") (pin "2") (pinfunction "2_2") (pintype "passive"))
      (node (ref "R25") (pin "2") (pinfunction "2_2") (pintype "passive"))
      (node (ref "U3") (pin "6") (pinfunction "FB_6") (pintype "passive"))
    )
    (net (code "78") (name "Net-(U3-REFin)") (class "Default")
      (node (ref "R24") (pin "1") (pinfunction "1_1") (pintype "passive"))
      (node (ref "R26") (pin "1") (pinfunction "1_1") (pintype "passive"))
      (node (ref "U3") (pin "7") (pinfunction "REFin_7") (pintype "passive"))
    )
    (net (code "79") (name "Net-(U3-RS-)") (class "Default")
      (node (ref "R27") (pin "2") (pintype "passive"))
      (node (ref "U3") (pin "2") (pinfunction "RS-_2") (pintype "passive"))
    )
    (net (code "80") (name "unconnected-(IC1-PA3-Pad17)") (class "Default")
      (node (ref "IC1") (pin "17") (pinfunction "PA3_17") (pintype "bidirectional"))
    )
    (net (code "81") (name "unconnected-(IC1-PB2{slash}BOOT1-Pad28)") (class "Default")
      (node (ref "IC1") (pin "28") (pinfunction "PB2/BOOT1_28") (pintype "bidirectional"))
    )
    (net (code "82") (name "unconnected-(IC1-PB8-Pad61)") (class "Default")
      (node (ref "IC1") (pin "61") (pinfunction "PB8_61") (pintype "bidirectional"))
    )
    (net (code "83") (name "unconnected-(IC1-PB12-Pad33)") (class "Default")
      (node (ref "IC1") (pin "33") (pinfunction "PB12_33") (pintype "bidirectional"))
    )
    (net (code "84") (name "unconnected-(IC1-PC5-Pad25)") (class "Default")
      (node (ref "IC1") (pin "25") (pinfunction "PC5_25") (pintype "bidirectional"))
    )
    (net (code "85") (name "unconnected-(IC1-PC8-Pad39)") (class "Default")
      (node (ref "IC1") (pin "39") (pinfunction "PC8_39") (pintype "bidirectional"))
    )
    (net (code "86") (name "unconnected-(IC1-PC9-Pad40)") (class "Default")
      (node (ref "IC1") (pin "40") (pinfunction "PC9_40") (pintype "bidirectional"))
    )
    (net (code "87") (name "unconnected-(IC1-PC13-TAMPER-RTC-Pad2)") (class "Default")
      (node (ref "IC1") (pin "2") (pinfunction "PC13-TAMPER-RTC_2") (pintype "bidirectional"))
    )
    (net (code "88") (name "unconnected-(IC1-PC14-OSC32_IN-Pad3)") (class "Default")
      (node (ref "IC1") (pin "3") (pinfunction "PC14-OSC32_IN_3") (pintype "bidirectional"))
    )
    (net (code "89") (name "unconnected-(IC1-PC15-OSC32_OUT-Pad4)") (class "Default")
      (node (ref "IC1") (pin "4") (pinfunction "PC15-OSC32_OUT_4") (pintype "bidirectional"))
    )
  )
)
